# ADC_Connectors.net
KiCad netlist of a schematic drawn in Altium Designer
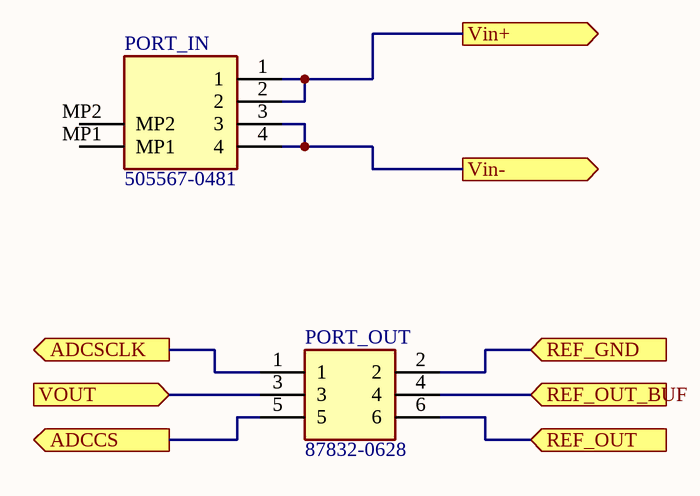
[diagram p0: ADC_Connectors.SchDoc]

(export (version "E")
  (design (tool "Eeschema 10.0.6"))
  (components
    (comp (ref "PORT_IN")
      (value "505567-0481")
      (footprint "SamacSys:5055670481")
      (description "Connector")
      (libsource (lib "*") (part "505567-0481"))
    )
    (comp (ref "PORT_OUT")
      (value "87832-0628")
      (footprint "SamacSys:878320628")
      (description "Connector")
      (libsource (lib "*") (part "87832-0628"))
    )
  )
  (nets
    (net (code "1") (name "/ADCCS") (class "Default")
      (node (ref "PORT_OUT") (pin "5") (pinfunction "5_5") (pintype "passive"))
    )
    (net (code "2") (name "/ADCSCLK") (class "Default")
      (node (ref "PORT_OUT") (pin "1") (pinfunction "1_1") (pintype "passive"))
    )
    (net (code "3") (name "/REF_GND") (class "Default")
      (node (ref "PORT_OUT") (pin "2") (pinfunction "2_2") (pintype "passive"))
    )
    (net (code "4") (name "/REF_OUT") (class "Default")
      (node (ref "PORT_OUT") (pin "6") (pinfunction "6_6") (pintype "passive"))
    )
    (net (code "5") (name "/REF_OUT_BUF") (class "Default")
      (node (ref "PORT_OUT") (pin "4") (pinfunction "4_4") (pintype "passive"))
    )
    (net (code "6") (name "/VOUT") (class "Default")
      (node (ref "PORT_OUT") (pin "3") (pinfunction "3_3") (pintype "passive"))
    )
    (net (code "7") (name "/Vin+") (class "Default")
      (node (ref "PORT_IN") (pin "1") (pinfunction "1_1") (pintype "passive"))
      (node (ref "PORT_IN") (pin "2") (pinfunction "2_2") (pintype "passive"))
    )
    (net (code "8") (name "/Vin-") (class "Default")
      (node (ref "PORT_IN") (pin "3") (pinfunction "3_3") (pintype "passive"))
      (node (ref "PORT_IN") (pin "4") (pinfunction "4_4") (pintype "passive"))
    )
    (net (code "9") (name "unconnected-(PORT_IN-PadMP1)") (class "Default")
      (node (ref "PORT_IN") (pin "MP1") (pinfunction "MP1_MP1") (pintype "passive"))
    )
    (net (code "10") (name "unconnected-(PORT_IN-PadMP2)") (class "Default")
      (node (ref "PORT_IN") (pin "MP2") (pinfunction "MP2_MP2") (pintype "passive"))
    )
  )
)
